# Nu6509_v4.net
KiCad netlist of a schematic drawn in EAGLE
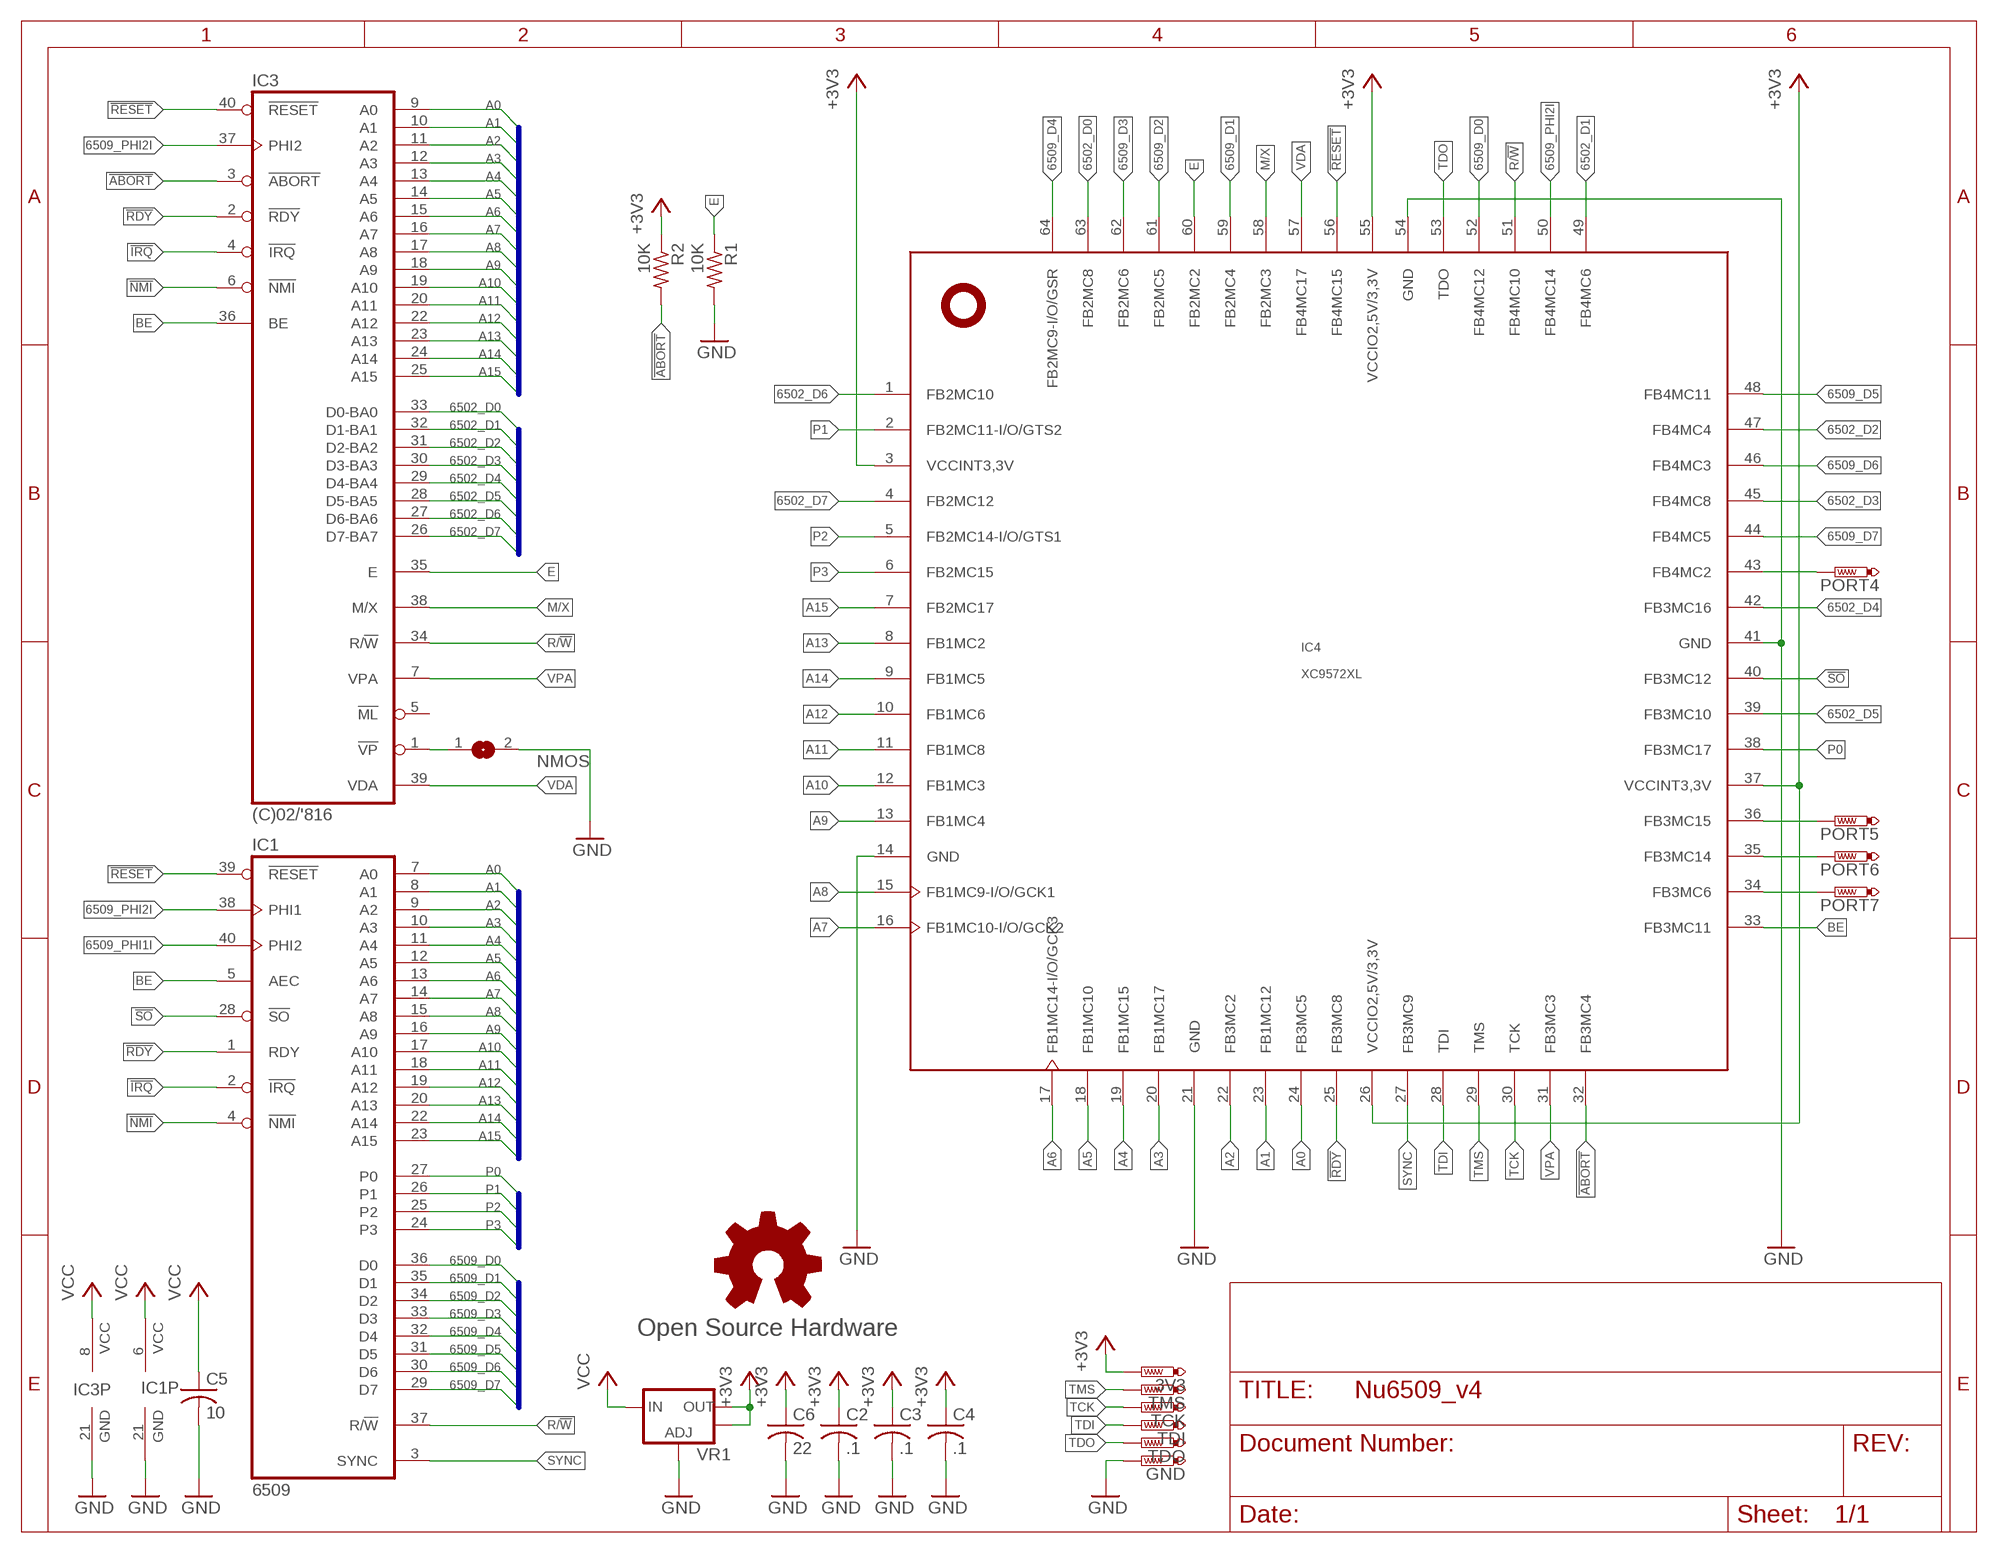
[diagram p0: schematic, sheet 1]

(export (version "E")
  (design (tool "Eeschema 10.0.6"))
  (components
    (comp (ref "3V3")
      (value "PTR1TP08R")
      (footprint "eagle-import:TP08R")
      (libsource (lib "eagle-import") (part "PTR1TP08R"))
    )
    (comp (ref "C2")
      (value ".1")
      (footprint "eagle-import:C0402")
      (libsource (lib "eagle-import") (part "C-USC0402"))
    )
    (comp (ref "C3")
      (value ".1")
      (footprint "eagle-import:C0402")
      (libsource (lib "eagle-import") (part "C-USC0402"))
    )
    (comp (ref "C4")
      (value ".1")
      (footprint "eagle-import:C0402")
      (libsource (lib "eagle-import") (part "C-USC0402"))
    )
    (comp (ref "C5")
      (value "10")
      (footprint "eagle-import:C0805")
      (libsource (lib "eagle-import") (part "C-USC0805"))
    )
    (comp (ref "C6")
      (value "22")
      (footprint "eagle-import:C0805")
      (libsource (lib "eagle-import") (part "C-USC0805"))
    )
    (comp (ref "GND")
      (value "PTR1TP08R")
      (footprint "eagle-import:TP08R")
      (libsource (lib "eagle-import") (part "PTR1TP08R"))
    )
    (comp (ref "GOLD_ORB_SM1")
      (value "Open Source Hardware")
      (footprint "eagle-import:OSHW_5MM")
      (libsource (lib "eagle-import") (part "OSHWLOGOLOGO5MM"))
    )
    (comp (ref "IC1")
      (value "6509")
      (footprint "eagle-import:DIL40-ROUNDPAD")
      (libsource (lib "eagle-import") (part "6509-RP"))
    )
    (comp (ref "IC3")
      (value "(C)02/'816")
      (footprint "eagle-import:DIL40-ROUNDPAD")
      (libsource (lib "eagle-import") (part "W65C816SP-RP"))
    )
    (comp (ref "IC4")
      (value "XC9572XL")
      (footprint "eagle-import:VQFP64")
      (libsource (lib "eagle-import") (part "XC9572XLVQG64"))
    )
    (comp (ref "NMOS")
      (value "SJ")
      (footprint "eagle-import:SJ")
      (libsource (lib "eagle-import") (part "SJ"))
    )
    (comp (ref "PORT4")
      (value "PTR1TP08R")
      (footprint "eagle-import:TP08R")
      (libsource (lib "eagle-import") (part "PTR1TP08R"))
    )
    (comp (ref "PORT5")
      (value "PTR1TP08R")
      (footprint "eagle-import:TP08R")
      (libsource (lib "eagle-import") (part "PTR1TP08R"))
    )
    (comp (ref "PORT6")
      (value "PTR1TP08R")
      (footprint "eagle-import:TP08R")
      (libsource (lib "eagle-import") (part "PTR1TP08R"))
    )
    (comp (ref "PORT7")
      (value "PTR1TP08R")
      (footprint "eagle-import:TP08R")
      (libsource (lib "eagle-import") (part "PTR1TP08R"))
    )
    (comp (ref "R1")
      (value "10K")
      (footprint "eagle-import:R0402")
      (libsource (lib "eagle-import") (part "R-US_R0402"))
    )
    (comp (ref "R2")
      (value "10K")
      (footprint "eagle-import:R0402")
      (libsource (lib "eagle-import") (part "R-US_R0402"))
    )
    (comp (ref "TCK")
      (value "PTR1TP08R")
      (footprint "eagle-import:TP08R")
      (libsource (lib "eagle-import") (part "PTR1TP08R"))
    )
    (comp (ref "TDI")
      (value "PTR1TP08R")
      (footprint "eagle-import:TP08R")
      (libsource (lib "eagle-import") (part "PTR1TP08R"))
    )
    (comp (ref "TDO")
      (value "PTR1TP08R")
      (footprint "eagle-import:TP08R")
      (libsource (lib "eagle-import") (part "PTR1TP08R"))
    )
    (comp (ref "TMS")
      (value "PTR1TP08R")
      (footprint "eagle-import:TP08R")
      (libsource (lib "eagle-import") (part "PTR1TP08R"))
    )
    (comp (ref "VR1")
      (value "V_REG_LM1117SOT223")
      (footprint "eagle-import:SOT223")
      (libsource (lib "eagle-import") (part "V_REG_LM1117SOT223"))
    )
  )
  (nets
    (net (code "1") (name "+3V3") (class "Default")
      (node (ref "3V3") (pin "TP") (pinfunction "TP_TP") (pintype "input"))
      (node (ref "C2") (pin "1") (pinfunction "1_1") (pintype "passive"))
      (node (ref "C3") (pin "1") (pinfunction "1_1") (pintype "passive"))
      (node (ref "C4") (pin "1") (pinfunction "1_1") (pintype "passive"))
      (node (ref "C6") (pin "1") (pinfunction "1_1") (pintype "passive"))
      (node (ref "IC4") (pin "26") (pinfunction "VCCIO2,5V/3,3V_26") (pintype "power_in"))
      (node (ref "IC4") (pin "3") (pinfunction "VCCINT3,3V_3") (pintype "power_in"))
      (node (ref "IC4") (pin "37") (pinfunction "VCCINT3,3V_37") (pintype "power_in"))
      (node (ref "IC4") (pin "55") (pinfunction "VCCIO2,5V/3,3V_55") (pintype "power_in"))
      (node (ref "R2") (pin "1") (pinfunction "1_1") (pintype "passive"))
      (node (ref "VR1") (pin "2") (pinfunction "OUT_2") (pintype "output"))
      (node (ref "VR1") (pin "4") (pinfunction "OUT_4") (pintype "output"))
    )
    (net (code "2") (name "/R{slash}~{W}") (class "Default")
      (node (ref "IC1") (pin "37") (pinfunction "R/~{W}_37") (pintype "output"))
      (node (ref "IC3") (pin "34") (pinfunction "R/~{W}_34") (pintype "output"))
      (node (ref "IC4") (pin "51") (pinfunction "FB4MC10_51") (pintype "bidirectional"))
    )
    (net (code "3") (name "/~{ABORT}") (class "Default")
      (node (ref "IC3") (pin "3") (pinfunction "~{ABORT}_3") (pintype "input"))
      (node (ref "IC4") (pin "32") (pinfunction "FB3MC4_32") (pintype "bidirectional"))
      (node (ref "R2") (pin "2") (pinfunction "2_2") (pintype "passive"))
    )
    (net (code "4") (name "/~{IRQ}") (class "Default")
      (node (ref "IC1") (pin "2") (pinfunction "~{IRQ}_2") (pintype "input"))
      (node (ref "IC3") (pin "4") (pinfunction "~{IRQ}_4") (pintype "input"))
    )
    (net (code "5") (name "/~{NMI}") (class "Default")
      (node (ref "IC1") (pin "4") (pinfunction "~{NMI}_4") (pintype "input"))
      (node (ref "IC3") (pin "6") (pinfunction "~{NMI}_6") (pintype "input"))
    )
    (net (code "6") (name "/~{RDY}") (class "Default")
      (node (ref "IC1") (pin "1") (pinfunction "RDY_1") (pintype "input"))
      (node (ref "IC3") (pin "2") (pinfunction "~{RDY}_2") (pintype "bidirectional"))
      (node (ref "IC4") (pin "25") (pinfunction "FB3MC8_25") (pintype "bidirectional"))
    )
    (net (code "7") (name "/~{RESET}") (class "Default")
      (node (ref "IC1") (pin "39") (pinfunction "~{RESET}_39") (pintype "input"))
      (node (ref "IC3") (pin "40") (pinfunction "~{RESET}_40") (pintype "input"))
      (node (ref "IC4") (pin "56") (pinfunction "FB4MC15_56") (pintype "bidirectional"))
    )
    (net (code "8") (name "/~{SO}") (class "Default")
      (node (ref "IC1") (pin "28") (pinfunction "~{SO}_28") (pintype "input"))
      (node (ref "IC4") (pin "40") (pinfunction "FB3MC12_40") (pintype "bidirectional"))
    )
    (net (code "9") (name "6502_D0") (class "Default")
      (node (ref "IC3") (pin "33") (pinfunction "D0-BA0_33") (pintype "bidirectional"))
      (node (ref "IC4") (pin "63") (pinfunction "FB2MC8_63") (pintype "bidirectional"))
    )
    (net (code "10") (name "6502_D1") (class "Default")
      (node (ref "IC3") (pin "32") (pinfunction "D1-BA1_32") (pintype "bidirectional"))
      (node (ref "IC4") (pin "49") (pinfunction "FB4MC6_49") (pintype "bidirectional"))
    )
    (net (code "11") (name "6502_D2") (class "Default")
      (node (ref "IC3") (pin "31") (pinfunction "D2-BA2_31") (pintype "bidirectional"))
      (node (ref "IC4") (pin "47") (pinfunction "FB4MC4_47") (pintype "bidirectional"))
    )
    (net (code "12") (name "6502_D3") (class "Default")
      (node (ref "IC3") (pin "30") (pinfunction "D3-BA3_30") (pintype "bidirectional"))
      (node (ref "IC4") (pin "45") (pinfunction "FB4MC8_45") (pintype "bidirectional"))
    )
    (net (code "13") (name "6502_D4") (class "Default")
      (node (ref "IC3") (pin "29") (pinfunction "D4-BA4_29") (pintype "bidirectional"))
      (node (ref "IC4") (pin "42") (pinfunction "FB3MC16_42") (pintype "bidirectional"))
    )
    (net (code "14") (name "6502_D5") (class "Default")
      (node (ref "IC3") (pin "28") (pinfunction "D5-BA5_28") (pintype "bidirectional"))
      (node (ref "IC4") (pin "39") (pinfunction "FB3MC10_39") (pintype "bidirectional"))
    )
    (net (code "15") (name "6502_D6") (class "Default")
      (node (ref "IC3") (pin "27") (pinfunction "D6-BA6_27") (pintype "bidirectional"))
      (node (ref "IC4") (pin "1") (pinfunction "FB2MC10_1") (pintype "bidirectional"))
    )
    (net (code "16") (name "6502_D7") (class "Default")
      (node (ref "IC3") (pin "26") (pinfunction "D7-BA7_26") (pintype "bidirectional"))
      (node (ref "IC4") (pin "4") (pinfunction "FB2MC12_4") (pintype "bidirectional"))
    )
    (net (code "17") (name "6509_D0") (class "Default")
      (node (ref "IC1") (pin "36") (pinfunction "D0_36") (pintype "bidirectional"))
      (node (ref "IC4") (pin "52") (pinfunction "FB4MC12_52") (pintype "bidirectional"))
    )
    (net (code "18") (name "6509_D1") (class "Default")
      (node (ref "IC1") (pin "35") (pinfunction "D1_35") (pintype "bidirectional"))
      (node (ref "IC4") (pin "59") (pinfunction "FB2MC4_59") (pintype "bidirectional"))
    )
    (net (code "19") (name "6509_D2") (class "Default")
      (node (ref "IC1") (pin "34") (pinfunction "D2_34") (pintype "bidirectional"))
      (node (ref "IC4") (pin "61") (pinfunction "FB2MC5_61") (pintype "bidirectional"))
    )
    (net (code "20") (name "6509_D3") (class "Default")
      (node (ref "IC1") (pin "33") (pinfunction "D3_33") (pintype "bidirectional"))
      (node (ref "IC4") (pin "62") (pinfunction "FB2MC6_62") (pintype "bidirectional"))
    )
    (net (code "21") (name "6509_D4") (class "Default")
      (node (ref "IC1") (pin "32") (pinfunction "D4_32") (pintype "bidirectional"))
      (node (ref "IC4") (pin "64") (pinfunction "FB2MC9-I/O/GSR_64") (pintype "bidirectional"))
    )
    (net (code "22") (name "6509_D5") (class "Default")
      (node (ref "IC1") (pin "31") (pinfunction "D5_31") (pintype "bidirectional"))
      (node (ref "IC4") (pin "48") (pinfunction "FB4MC11_48") (pintype "bidirectional"))
    )
    (net (code "23") (name "6509_D6") (class "Default")
      (node (ref "IC1") (pin "30") (pinfunction "D6_30") (pintype "bidirectional"))
      (node (ref "IC4") (pin "46") (pinfunction "FB4MC3_46") (pintype "bidirectional"))
    )
    (net (code "24") (name "6509_D7") (class "Default")
      (node (ref "IC1") (pin "29") (pinfunction "D7_29") (pintype "bidirectional"))
      (node (ref "IC4") (pin "44") (pinfunction "FB4MC5_44") (pintype "bidirectional"))
    )
    (net (code "25") (name "6509_PHI1I") (class "Default")
      (node (ref "IC1") (pin "40") (pinfunction "PHI2_40") (pintype "input"))
    )
    (net (code "26") (name "6509_PHI2I") (class "Default")
      (node (ref "IC1") (pin "38") (pinfunction "PHI1_38") (pintype "input"))
      (node (ref "IC3") (pin "37") (pinfunction "PHI2_37") (pintype "input"))
      (node (ref "IC4") (pin "50") (pinfunction "FB4MC14_50") (pintype "bidirectional"))
    )
    (net (code "27") (name "A0") (class "Default")
      (node (ref "IC1") (pin "7") (pinfunction "A0_7") (pintype "output"))
      (node (ref "IC3") (pin "9") (pinfunction "A0_9") (pintype "tri_state"))
      (node (ref "IC4") (pin "24") (pinfunction "FB3MC5_24") (pintype "bidirectional"))
    )
    (net (code "28") (name "A1") (class "Default")
      (node (ref "IC1") (pin "8") (pinfunction "A1_8") (pintype "output"))
      (node (ref "IC3") (pin "10") (pinfunction "A1_10") (pintype "tri_state"))
      (node (ref "IC4") (pin "23") (pinfunction "FB1MC12_23") (pintype "bidirectional"))
    )
    (net (code "29") (name "A2") (class "Default")
      (node (ref "IC1") (pin "9") (pinfunction "A2_9") (pintype "output"))
      (node (ref "IC3") (pin "11") (pinfunction "A2_11") (pintype "tri_state"))
      (node (ref "IC4") (pin "22") (pinfunction "FB3MC2_22") (pintype "bidirectional"))
    )
    (net (code "30") (name "A3") (class "Default")
      (node (ref "IC1") (pin "10") (pinfunction "A3_10") (pintype "output"))
      (node (ref "IC3") (pin "12") (pinfunction "A3_12") (pintype "tri_state"))
      (node (ref "IC4") (pin "20") (pinfunction "FB1MC17_20") (pintype "bidirectional"))
    )
    (net (code "31") (name "A4") (class "Default")
      (node (ref "IC1") (pin "11") (pinfunction "A4_11") (pintype "output"))
      (node (ref "IC3") (pin "13") (pinfunction "A4_13") (pintype "tri_state"))
      (node (ref "IC4") (pin "19") (pinfunction "FB1MC15_19") (pintype "bidirectional"))
    )
    (net (code "32") (name "A5") (class "Default")
      (node (ref "IC1") (pin "12") (pinfunction "A5_12") (pintype "output"))
      (node (ref "IC3") (pin "14") (pinfunction "A5_14") (pintype "tri_state"))
      (node (ref "IC4") (pin "18") (pinfunction "FB1MC10_18") (pintype "bidirectional"))
    )
    (net (code "33") (name "A6") (class "Default")
      (node (ref "IC1") (pin "13") (pinfunction "A6_13") (pintype "output"))
      (node (ref "IC3") (pin "15") (pinfunction "A6_15") (pintype "tri_state"))
      (node (ref "IC4") (pin "17") (pinfunction "FB1MC14-I/O/GCK3_17") (pintype "bidirectional"))
    )
    (net (code "34") (name "A7") (class "Default")
      (node (ref "IC1") (pin "14") (pinfunction "A7_14") (pintype "output"))
      (node (ref "IC3") (pin "16") (pinfunction "A7_16") (pintype "tri_state"))
      (node (ref "IC4") (pin "16") (pinfunction "FB1MC10-I/O/GCK2_16") (pintype "bidirectional"))
    )
    (net (code "35") (name "A8") (class "Default")
      (node (ref "IC1") (pin "15") (pinfunction "A8_15") (pintype "output"))
      (node (ref "IC3") (pin "17") (pinfunction "A8_17") (pintype "tri_state"))
      (node (ref "IC4") (pin "15") (pinfunction "FB1MC9-I/O/GCK1_15") (pintype "bidirectional"))
    )
    (net (code "36") (name "A9") (class "Default")
      (node (ref "IC1") (pin "16") (pinfunction "A9_16") (pintype "output"))
      (node (ref "IC3") (pin "18") (pinfunction "A9_18") (pintype "tri_state"))
      (node (ref "IC4") (pin "13") (pinfunction "FB1MC4_13") (pintype "bidirectional"))
    )
    (net (code "37") (name "A10") (class "Default")
      (node (ref "IC1") (pin "17") (pinfunction "A10_17") (pintype "output"))
      (node (ref "IC3") (pin "19") (pinfunction "A10_19") (pintype "tri_state"))
      (node (ref "IC4") (pin "12") (pinfunction "FB1MC3_12") (pintype "bidirectional"))
    )
    (net (code "38") (name "A11") (class "Default")
      (node (ref "IC1") (pin "18") (pinfunction "A11_18") (pintype "output"))
      (node (ref "IC3") (pin "20") (pinfunction "A11_20") (pintype "tri_state"))
      (node (ref "IC4") (pin "11") (pinfunction "FB1MC8_11") (pintype "bidirectional"))
    )
    (net (code "39") (name "A12") (class "Default")
      (node (ref "IC1") (pin "19") (pinfunction "A12_19") (pintype "output"))
      (node (ref "IC3") (pin "22") (pinfunction "A12_22") (pintype "tri_state"))
      (node (ref "IC4") (pin "10") (pinfunction "FB1MC6_10") (pintype "bidirectional"))
    )
    (net (code "40") (name "A13") (class "Default")
      (node (ref "IC1") (pin "20") (pinfunction "A13_20") (pintype "output"))
      (node (ref "IC3") (pin "23") (pinfunction "A13_23") (pintype "tri_state"))
      (node (ref "IC4") (pin "8") (pinfunction "FB1MC2_8") (pintype "bidirectional"))
    )
    (net (code "41") (name "A14") (class "Default")
      (node (ref "IC1") (pin "22") (pinfunction "A14_22") (pintype "output"))
      (node (ref "IC3") (pin "24") (pinfunction "A14_24") (pintype "tri_state"))
      (node (ref "IC4") (pin "9") (pinfunction "FB1MC5_9") (pintype "bidirectional"))
    )
    (net (code "42") (name "A15") (class "Default")
      (node (ref "IC1") (pin "23") (pinfunction "A15_23") (pintype "output"))
      (node (ref "IC3") (pin "25") (pinfunction "A15_25") (pintype "tri_state"))
      (node (ref "IC4") (pin "7") (pinfunction "FB2MC17_7") (pintype "bidirectional"))
    )
    (net (code "43") (name "BE") (class "Default")
      (node (ref "IC1") (pin "5") (pinfunction "AEC_5") (pintype "input"))
      (node (ref "IC3") (pin "36") (pinfunction "BE_36") (pintype "input"))
      (node (ref "IC4") (pin "33") (pinfunction "FB3MC11_33") (pintype "bidirectional"))
    )
    (net (code "44") (name "E") (class "Default")
      (node (ref "IC3") (pin "35") (pinfunction "E_35") (pintype "output"))
      (node (ref "IC4") (pin "60") (pinfunction "FB2MC2_60") (pintype "bidirectional"))
      (node (ref "R1") (pin "1") (pinfunction "1_1") (pintype "passive"))
    )
    (net (code "45") (name "GND") (class "Default")
      (node (ref "C2") (pin "2") (pinfunction "2_2") (pintype "passive"))
      (node (ref "C3") (pin "2") (pinfunction "2_2") (pintype "passive"))
      (node (ref "C4") (pin "2") (pinfunction "2_2") (pintype "passive"))
      (node (ref "C5") (pin "2") (pinfunction "2_2") (pintype "passive"))
      (node (ref "C6") (pin "2") (pinfunction "2_2") (pintype "passive"))
      (node (ref "GND") (pin "TP") (pinfunction "TP_TP") (pintype "input"))
      (node (ref "IC1") (pin "21") (pinfunction "GND_21") (pintype "power_in"))
      (node (ref "IC3") (pin "21") (pinfunction "GND_21") (pintype "power_in"))
      (node (ref "IC4") (pin "14") (pinfunction "GND_14") (pintype "power_in"))
      (node (ref "IC4") (pin "21") (pinfunction "GND_21") (pintype "power_in"))
      (node (ref "IC4") (pin "41") (pinfunction "GND_41") (pintype "power_in"))
      (node (ref "IC4") (pin "54") (pinfunction "GND_54") (pintype "power_in"))
      (node (ref "NMOS") (pin "2") (pinfunction "2_2") (pintype "passive"))
      (node (ref "R1") (pin "2") (pinfunction "2_2") (pintype "passive"))
      (node (ref "VR1") (pin "1") (pinfunction "ADJ_1") (pintype "input"))
    )
    (net (code "46") (name "M{slash}X") (class "Default")
      (node (ref "IC3") (pin "38") (pinfunction "M/X_38") (pintype "output"))
      (node (ref "IC4") (pin "58") (pinfunction "FB2MC3_58") (pintype "bidirectional"))
    )
    (net (code "47") (name "Net-(IC3A-~{VP})") (class "Default")
      (node (ref "IC3") (pin "1") (pinfunction "~{VP}_1") (pintype "output"))
      (node (ref "NMOS") (pin "1") (pinfunction "1_1") (pintype "passive"))
    )
    (net (code "48") (name "Net-(IC4-FB3MC6)") (class "Default")
      (node (ref "IC4") (pin "34") (pinfunction "FB3MC6_34") (pintype "bidirectional"))
      (node (ref "PORT7") (pin "TP") (pinfunction "TP_TP") (pintype "input"))
    )
    (net (code "49") (name "Net-(IC4-FB3MC14)") (class "Default")
      (node (ref "IC4") (pin "35") (pinfunction "FB3MC14_35") (pintype "bidirectional"))
      (node (ref "PORT6") (pin "TP") (pinfunction "TP_TP") (pintype "input"))
    )
    (net (code "50") (name "Net-(IC4-FB3MC15)") (class "Default")
      (node (ref "IC4") (pin "36") (pinfunction "FB3MC15_36") (pintype "bidirectional"))
      (node (ref "PORT5") (pin "TP") (pinfunction "TP_TP") (pintype "input"))
    )
    (net (code "51") (name "Net-(IC4-FB4MC2)") (class "Default")
      (node (ref "IC4") (pin "43") (pinfunction "FB4MC2_43") (pintype "bidirectional"))
      (node (ref "PORT4") (pin "TP") (pinfunction "TP_TP") (pintype "input"))
    )
    (net (code "52") (name "P0") (class "Default")
      (node (ref "IC1") (pin "27") (pinfunction "P0_27") (pintype "output"))
      (node (ref "IC4") (pin "38") (pinfunction "FB3MC17_38") (pintype "bidirectional"))
    )
    (net (code "53") (name "P1") (class "Default")
      (node (ref "IC1") (pin "26") (pinfunction "P1_26") (pintype "output"))
      (node (ref "IC4") (pin "2") (pinfunction "FB2MC11-I/O/GTS2_2") (pintype "bidirectional"))
    )
    (net (code "54") (name "P2") (class "Default")
      (node (ref "IC1") (pin "25") (pinfunction "P2_25") (pintype "output"))
      (node (ref "IC4") (pin "5") (pinfunction "FB2MC14-I/O/GTS1_5") (pintype "bidirectional"))
    )
    (net (code "55") (name "P3") (class "Default")
      (node (ref "IC1") (pin "24") (pinfunction "P3_24") (pintype "output"))
      (node (ref "IC4") (pin "6") (pinfunction "FB2MC15_6") (pintype "bidirectional"))
    )
    (net (code "56") (name "SYNC") (class "Default")
      (node (ref "IC1") (pin "3") (pinfunction "SYNC_3") (pintype "output"))
      (node (ref "IC4") (pin "27") (pinfunction "FB3MC9_27") (pintype "bidirectional"))
    )
    (net (code "57") (name "TCK") (class "Default")
      (node (ref "IC4") (pin "30") (pinfunction "TCK_30") (pintype "bidirectional"))
      (node (ref "TCK") (pin "TP") (pinfunction "TP_TP") (pintype "input"))
    )
    (net (code "58") (name "TDI") (class "Default")
      (node (ref "IC4") (pin "28") (pinfunction "TDI_28") (pintype "bidirectional"))
      (node (ref "TDI") (pin "TP") (pinfunction "TP_TP") (pintype "input"))
    )
    (net (code "59") (name "TDO") (class "Default")
      (node (ref "IC4") (pin "53") (pinfunction "TDO_53") (pintype "bidirectional"))
      (node (ref "TDO") (pin "TP") (pinfunction "TP_TP") (pintype "input"))
    )
    (net (code "60") (name "TMS") (class "Default")
      (node (ref "IC4") (pin "29") (pinfunction "TMS_29") (pintype "bidirectional"))
      (node (ref "TMS") (pin "TP") (pinfunction "TP_TP") (pintype "input"))
    )
    (net (code "61") (name "VCC") (class "Default")
      (node (ref "C5") (pin "1") (pinfunction "1_1") (pintype "passive"))
      (node (ref "IC1") (pin "6") (pinfunction "VCC_6") (pintype "power_in"))
      (node (ref "IC3") (pin "8") (pinfunction "VCC_8") (pintype "power_in"))
      (node (ref "VR1") (pin "3") (pinfunction "IN_3") (pintype "input"))
    )
    (net (code "62") (name "VDA") (class "Default")
      (node (ref "IC3") (pin "39") (pinfunction "VDA_39") (pintype "output"))
      (node (ref "IC4") (pin "57") (pinfunction "FB4MC17_57") (pintype "bidirectional"))
    )
    (net (code "63") (name "VPA") (class "Default")
      (node (ref "IC3") (pin "7") (pinfunction "VPA_7") (pintype "output"))
      (node (ref "IC4") (pin "31") (pinfunction "FB3MC3_31") (pintype "bidirectional"))
    )
    (net (code "64") (name "unconnected-(IC3A-~{ML}-Pad5)") (class "Default")
      (node (ref "IC3") (pin "5") (pinfunction "~{ML}_5") (pintype "output"))
    )
  )
)
